# ThermocoupleAmplifiersAD8494.net
KiCad netlist of a schematic drawn in Altium Designer
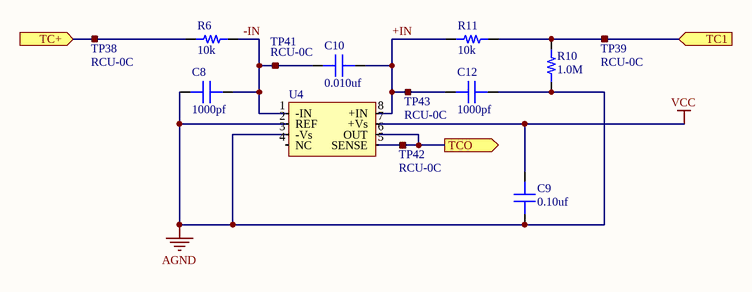
[diagram p0: ThermocoupleAmplifiersAD8494.SchDoc]

(export (version "E")
  (design (tool "Eeschema 10.0.6"))
  (components
    (comp (ref "C8")
      (value "1000pf")
      (footprint "CAP 0603/1608")
      (fields
        (field (name "Comment") "Capacitor MLCC 1000pf 16V CAP 0603/1608")
        (field (name "CREATED_BY") "Nick Mah")
      )
      (libsource (lib "Altium-Lib") (part "Capacitor"))
    )
    (comp (ref "C9")
      (value "0.10uf")
      (footprint "CAP 0603/1608")
      (fields
        (field (name "Comment") "Capacitor MLCC 0.10uf 16V CAP 0603/1608")
        (field (name "CREATED_BY") "Nick Mah")
      )
      (libsource (lib "Altium-Lib") (part "Capacitor"))
    )
    (comp (ref "C10")
      (value "0.010uf")
      (footprint "CAP 0603/1608")
      (fields
        (field (name "Comment") "Capacitor MLCC 0.010uf 16V CAP 0603/1608")
        (field (name "CREATED_BY") "Nick Mah")
      )
      (libsource (lib "Altium-Lib") (part "Capacitor"))
    )
    (comp (ref "C12")
      (value "1000pf")
      (footprint "CAP 0603/1608")
      (fields
        (field (name "Comment") "Capacitor MLCC 1000pf 16V CAP 0603/1608")
        (field (name "CREATED_BY") "Nick Mah")
      )
      (libsource (lib "Altium-Lib") (part "Capacitor"))
    )
    (comp (ref "R6")
      (value "10k")
      (footprint "RES 0603/1608")
      (fields
        (field (name "TOLERANCE") "10%")
        (field (name "POWER") "1/10W")
        (field (name "Comment") "Resistor 10k 0603 1/10W 10%")
        (field (name "CREATED_BY") "Nick Mah")
      )
      (libsource (lib "Altium-Lib") (part "Resistor"))
    )
    (comp (ref "R10")
      (value "1.0M")
      (footprint "RES 0603/1608")
      (fields
        (field (name "TOLERANCE") "5%")
        (field (name "POWER") "1/10W")
        (field (name "Comment") "Resistor 1.0M 0603 1/10W 5%")
        (field (name "CREATED_BY") "Nick Mah")
      )
      (libsource (lib "Altium-Lib") (part "Resistor"))
    )
    (comp (ref "R11")
      (value "10k")
      (footprint "RES 0603/1608")
      (fields
        (field (name "TOLERANCE") "10%")
        (field (name "POWER") "1/10W")
        (field (name "Comment") "Resistor 10k 0603 1/10W 10%")
        (field (name "CREATED_BY") "Nick Mah")
      )
      (libsource (lib "Altium-Lib") (part "Resistor"))
    )
    (comp (ref "TP38")
      (value "RCU-0C")
      (footprint "RCU-0C")
      (description "Test point")
      (fields (field (name "CREATED_BY") "Graydon") (field (name "UPDATED_BY") "Null"))
      (libsource (lib "Altium-Lib") (part "RCU-0C"))
    )
    (comp (ref "TP39")
      (value "RCU-0C")
      (footprint "RCU-0C")
      (description "Test point")
      (fields (field (name "CREATED_BY") "Graydon") (field (name "UPDATED_BY") "Null"))
      (libsource (lib "Altium-Lib") (part "RCU-0C"))
    )
    (comp (ref "TP41")
      (value "RCU-0C")
      (footprint "RCU-0C")
      (description "Test point")
      (fields (field (name "CREATED_BY") "Graydon") (field (name "UPDATED_BY") "Null"))
      (libsource (lib "Altium-Lib") (part "RCU-0C"))
    )
    (comp (ref "TP42")
      (value "RCU-0C")
      (footprint "RCU-0C")
      (description "Test point")
      (fields (field (name "CREATED_BY") "Graydon") (field (name "UPDATED_BY") "Null"))
      (libsource (lib "Altium-Lib") (part "RCU-0C"))
    )
    (comp (ref "TP43")
      (value "RCU-0C")
      (footprint "RCU-0C")
      (description "Test point")
      (fields (field (name "CREATED_BY") "Graydon") (field (name "UPDATED_BY") "Null"))
      (libsource (lib "Altium-Lib") (part "RCU-0C"))
    )
    (comp (ref "U4")
      (value "~")
      (footprint "MSOP-8")
      (description "IC THRMOCPLE COLD JNC COMP 8MSOP")
      (fields (field (name "MFRPARTNO") "AD8494CRMZ") (field (name "CREATED_BY") "Nick Mah"))
      (libsource (lib "Altium-Lib") (part "AD8494"))
    )
  )
  (nets
    (net (code "1") (name "/+IN") (class "Default")
      (node (ref "C10") (pin "2") (pinfunction "2_2") (pintype "passive"))
      (node (ref "C12") (pin "1") (pinfunction "1_1") (pintype "passive"))
      (node (ref "R11") (pin "1") (pinfunction "1_1") (pintype "passive"))
      (node (ref "TP43") (pin "1") (pintype "passive"))
      (node (ref "U4") (pin "8") (pinfunction "+IN_8") (pintype "input"))
    )
    (net (code "2") (name "/-IN") (class "Default")
      (node (ref "C10") (pin "1") (pinfunction "1_1") (pintype "passive"))
      (node (ref "C8") (pin "2") (pinfunction "2_2") (pintype "passive"))
      (node (ref "R6") (pin "2") (pinfunction "2_2") (pintype "passive"))
      (node (ref "TP41") (pin "1") (pintype "passive"))
      (node (ref "U4") (pin "1") (pinfunction "-IN_1") (pintype "input"))
    )
    (net (code "3") (name "/TC+") (class "Default")
      (node (ref "R6") (pin "1") (pinfunction "1_1") (pintype "passive"))
      (node (ref "TP38") (pin "1") (pintype "passive"))
    )
    (net (code "4") (name "/TC1") (class "Default")
      (node (ref "R10") (pin "2") (pinfunction "2_2") (pintype "passive"))
      (node (ref "R11") (pin "2") (pinfunction "2_2") (pintype "passive"))
      (node (ref "TP39") (pin "1") (pintype "passive"))
    )
    (net (code "5") (name "/TCO") (class "Default")
      (node (ref "TP42") (pin "1") (pintype "passive"))
      (node (ref "U4") (pin "5") (pinfunction "SENSE_5") (pintype "input"))
      (node (ref "U4") (pin "6") (pinfunction "OUT_6") (pintype "output"))
    )
    (net (code "6") (name "AGND") (class "Default")
      (node (ref "C12") (pin "2") (pinfunction "2_2") (pintype "passive"))
      (node (ref "C8") (pin "1") (pinfunction "1_1") (pintype "passive"))
      (node (ref "C9") (pin "1") (pinfunction "1_1") (pintype "passive"))
      (node (ref "R10") (pin "1") (pinfunction "1_1") (pintype "passive"))
      (node (ref "U4") (pin "2") (pinfunction "REF_2") (pintype "input"))
      (node (ref "U4") (pin "3") (pinfunction "-Vs_3") (pintype "power_in"))
    )
    (net (code "7") (name "VCC") (class "Default")
      (node (ref "C9") (pin "2") (pinfunction "2_2") (pintype "passive"))
      (node (ref "U4") (pin "7") (pinfunction "+Vs_7") (pintype "power_in"))
    )
    (net (code "8") (name "unconnected-(U4-NC-Pad4)") (class "Default")
      (node (ref "U4") (pin "4") (pinfunction "NC_4") (pintype "passive"))
    )
  )
)
